# POWER.net
KiCad netlist of a schematic drawn in Altium Designer
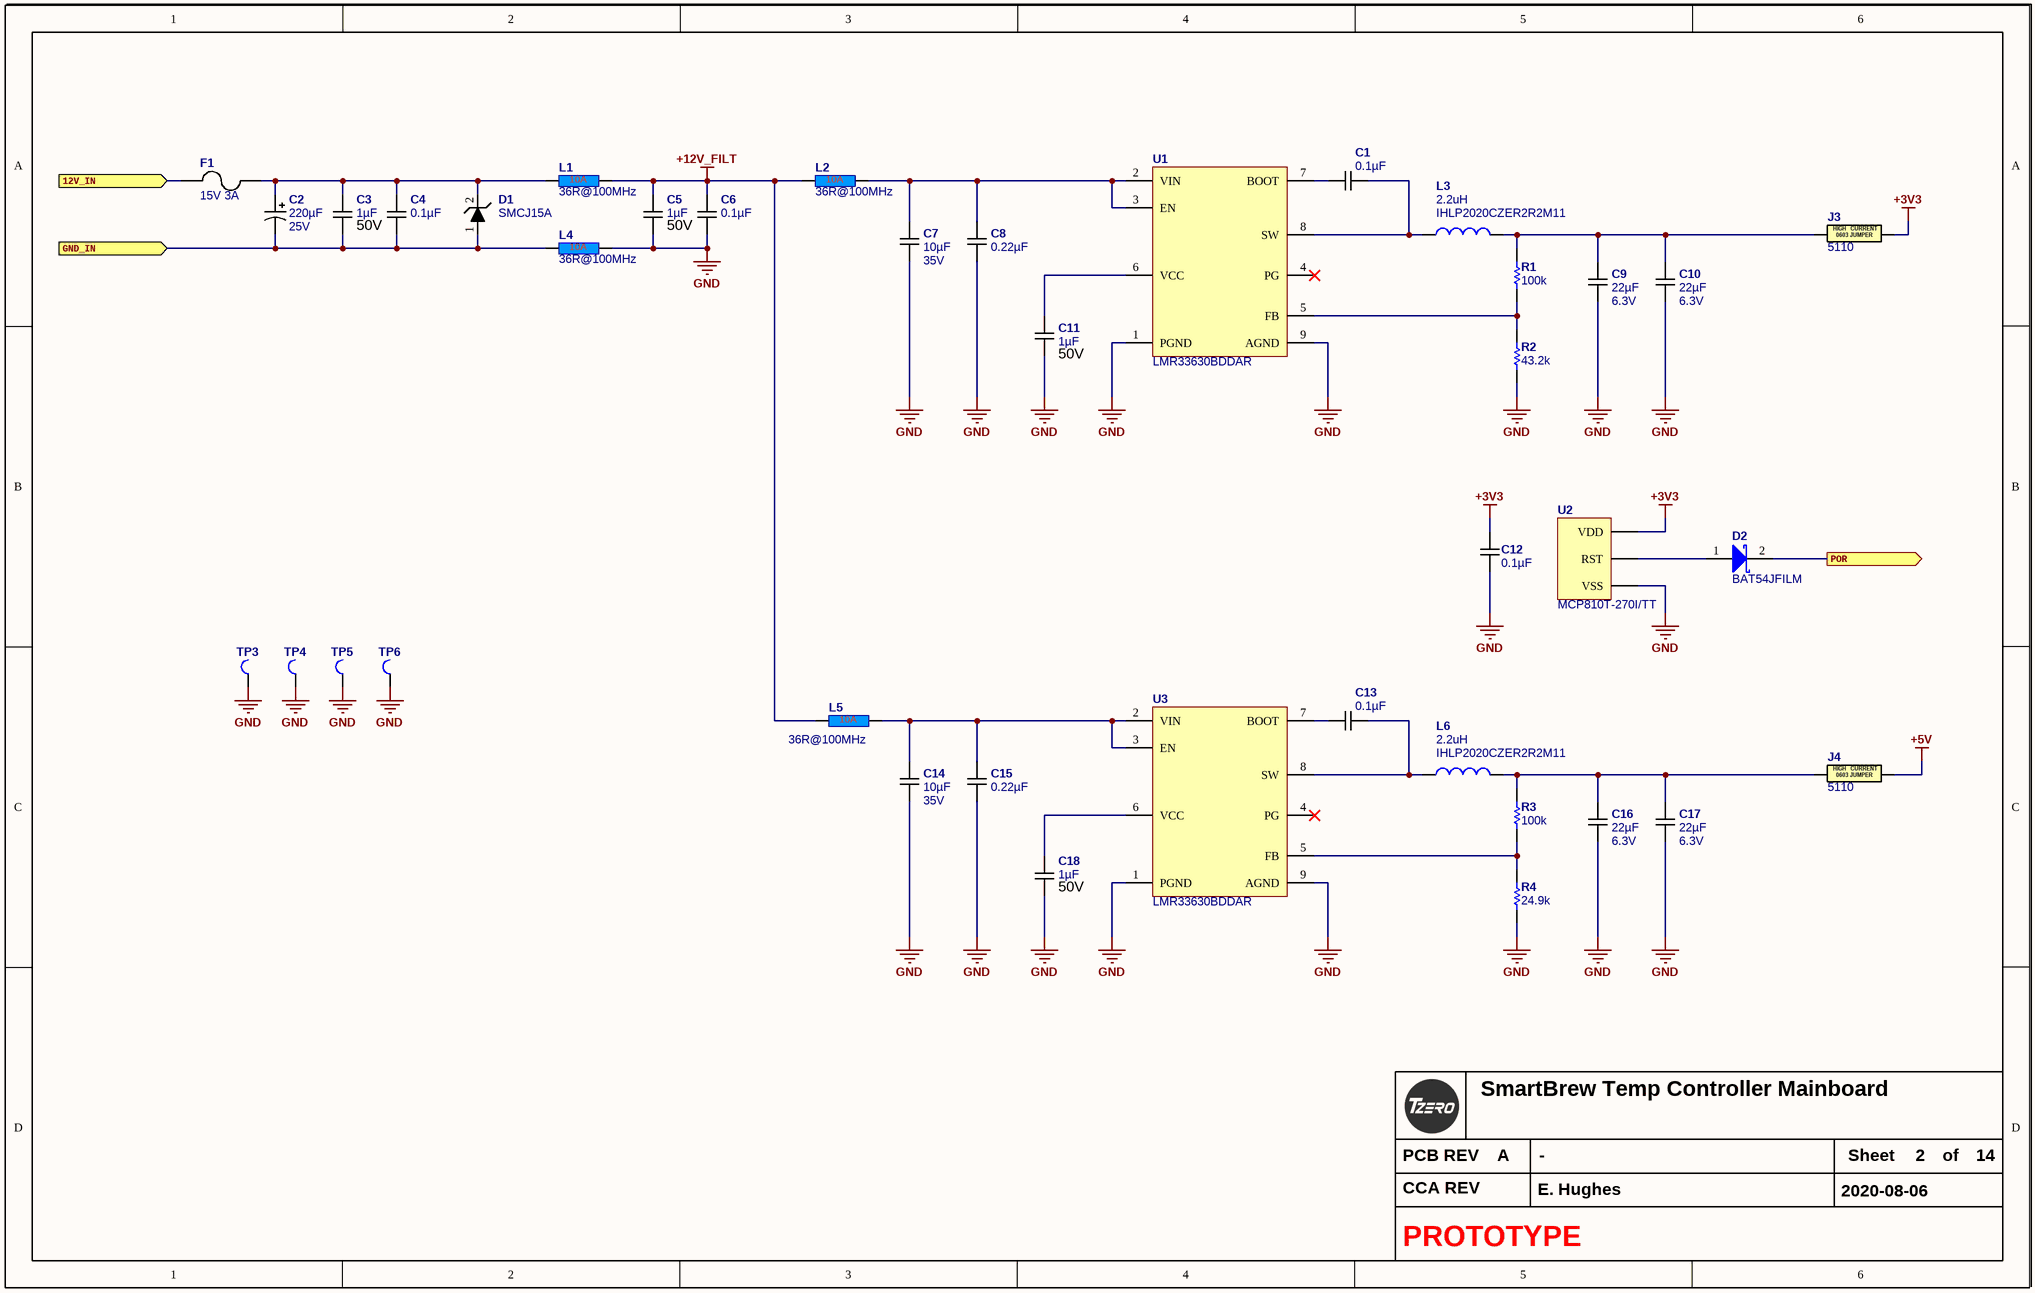
[diagram p0: POWER.SchDoc]

(export (version "E")
  (design (tool "Eeschema 10.0.6"))
  (components
    (comp (ref "C1")
      (value "0.1µF")
      (footprint "C0402_0.55MM_HD")
      (description "CAP CER 0.1UF 25V X7R 0402")
      (fields
        (field (name "MANUFACTURER PART NUMBER") "CGA2B3X7R1E104K050BB")
        (field (name "MANUFACTURER") "TDK Corporation")
      )
      (libsource (lib "Capacitors - TDK- AEC-Q200") (part "C_2P_NP"))
    )
    (comp (ref "C2")
      (value "220µF")
      (footprint "C_ALU_F")
      (description "CAP ALUM 220UF 25V 20% SMD")
      (fields
        (field (name "MANUFACTURER PART NUMBER") "EEE-FK1E221P")
        (field (name "MANUFACTURER") "Panasonic Electronic Components")
        (field (name "VOLTAGE RATING") "25V")
      )
      (libsource (lib "Capacitors - Panasonic - AluminumElectrolytic - AEC-Q200") (part "C_2P_P"))
    )
    (comp (ref "C3")
      (value "1µF")
      (footprint "C0805_1.50MM_MD")
      (description "CAP CER 1UF 50V X7R 0805")
      (fields
        (field (name "MANUFACTURER PART NUMBER") "CGA4J3X7R1H105M125AE")
        (field (name "MANUFACTURER") "TDK Corporation")
        (field (name "VOLTAGE - RATED") "50V")
      )
      (libsource (lib "Capacitors - TDK- AEC-Q200") (part "C_2P_NP"))
    )
    (comp (ref "C4")
      (value "0.1µF")
      (footprint "C0402_0.55MM_HD")
      (description "CAP CER 0.1UF 25V X7R 0402")
      (fields
        (field (name "MANUFACTURER PART NUMBER") "CGA2B3X7R1E104K050BB")
        (field (name "MANUFACTURER") "TDK Corporation")
      )
      (libsource (lib "Capacitors - TDK- AEC-Q200") (part "C_2P_NP"))
    )
    (comp (ref "C5")
      (value "1µF")
      (footprint "C0805_1.50MM_MD")
      (description "CAP CER 1UF 50V X7R 0805")
      (fields
        (field (name "MANUFACTURER PART NUMBER") "CGA4J3X7R1H105M125AE")
        (field (name "MANUFACTURER") "TDK Corporation")
        (field (name "VOLTAGE - RATED") "50V")
      )
      (libsource (lib "Capacitors - TDK- AEC-Q200") (part "C_2P_NP"))
    )
    (comp (ref "C6")
      (value "0.1µF")
      (footprint "C0402_0.55MM_HD")
      (description "CAP CER 0.1UF 25V X7R 0402")
      (fields
        (field (name "MANUFACTURER PART NUMBER") "CGA2B3X7R1E104K050BB")
        (field (name "MANUFACTURER") "TDK Corporation")
      )
      (libsource (lib "Capacitors - TDK- AEC-Q200") (part "C_2P_NP"))
    )
    (comp (ref "C7")
      (value "10µF")
      (footprint "C1206_1.90MM_HD")
      (description "CAP CER 10UF 35V X7R 1206")
      (fields
        (field (name "MANUFACTURER PART NUMBER") "CGA5L1X7R1V106M160AE")
        (field (name "MANUFACTURER") "TDK Corporation")
        (field (name "VOLTAGE - RATED") "35V")
      )
      (libsource (lib "Capacitors - TDK- AEC-Q200") (part "C_2P_NP"))
    )
    (comp (ref "C8")
      (value "0.22µF")
      (footprint "C0603_0.90MM_HD")
      (description "CAP CER 0.22UF 50V X7R 0603")
      (fields
        (field (name "MANUFACTURER PART NUMBER") "CGA3E3X7R1H224K080AB")
        (field (name "MANUFACTURER") "TDK Corporation")
      )
      (libsource (lib "Capacitors - TDK- AEC-Q200") (part "C_2P_NP"))
    )
    (comp (ref "C9")
      (value "22µF")
      (footprint "C1206_1.60MM_HD")
      (description "CAP CER 22UF 6.3V X7R 1206")
      (fields
        (field (name "MANUFACTURER PART NUMBER") "CGA5L1X7R0J226M160AC")
        (field (name "MANUFACTURER") "TDK Corporation")
        (field (name "VOLTAGE - RATED") "6.3V")
      )
      (libsource (lib "Capacitors - TDK- AEC-Q200") (part "C_2P_NP"))
    )
    (comp (ref "C10")
      (value "22µF")
      (footprint "C1206_1.60MM_HD")
      (description "CAP CER 22UF 6.3V X7R 1206")
      (fields
        (field (name "MANUFACTURER PART NUMBER") "CGA5L1X7R0J226M160AC")
        (field (name "MANUFACTURER") "TDK Corporation")
        (field (name "VOLTAGE - RATED") "6.3V")
      )
      (libsource (lib "Capacitors - TDK- AEC-Q200") (part "C_2P_NP"))
    )
    (comp (ref "C11")
      (value "1µF")
      (footprint "C0805_1.50MM_MD")
      (description "CAP CER 1UF 50V X7R 0805")
      (fields
        (field (name "MANUFACTURER PART NUMBER") "CGA4J3X7R1H105M125AE")
        (field (name "MANUFACTURER") "TDK Corporation")
        (field (name "VOLTAGE - RATED") "50V")
      )
      (libsource (lib "Capacitors - TDK- AEC-Q200") (part "C_2P_NP"))
    )
    (comp (ref "C12")
      (value "0.1µF")
      (footprint "C0402_0.55MM_HD")
      (description "CAP CER 0.1UF 25V X7R 0402")
      (fields
        (field (name "MANUFACTURER PART NUMBER") "CGA2B3X7R1E104K050BB")
        (field (name "MANUFACTURER") "TDK Corporation")
      )
      (libsource (lib "Capacitors - TDK- AEC-Q200") (part "C_2P_NP"))
    )
    (comp (ref "C13")
      (value "0.1µF")
      (footprint "C0402_0.55MM_HD")
      (description "CAP CER 0.1UF 25V X7R 0402")
      (fields
        (field (name "MANUFACTURER PART NUMBER") "CGA2B3X7R1E104K050BB")
        (field (name "MANUFACTURER") "TDK Corporation")
      )
      (libsource (lib "Capacitors - TDK- AEC-Q200") (part "C_2P_NP"))
    )
    (comp (ref "C14")
      (value "10µF")
      (footprint "C1206_1.90MM_HD")
      (description "CAP CER 10UF 35V X7R 1206")
      (fields
        (field (name "MANUFACTURER PART NUMBER") "CGA5L1X7R1V106M160AE")
        (field (name "MANUFACTURER") "TDK Corporation")
        (field (name "VOLTAGE - RATED") "35V")
      )
      (libsource (lib "Capacitors - TDK- AEC-Q200") (part "C_2P_NP"))
    )
    (comp (ref "C15")
      (value "0.22µF")
      (footprint "C0603_0.90MM_HD")
      (description "CAP CER 0.22UF 50V X7R 0603")
      (fields
        (field (name "MANUFACTURER PART NUMBER") "CGA3E3X7R1H224K080AB")
        (field (name "MANUFACTURER") "TDK Corporation")
      )
      (libsource (lib "Capacitors - TDK- AEC-Q200") (part "C_2P_NP"))
    )
    (comp (ref "C16")
      (value "22µF")
      (footprint "C1206_1.60MM_HD")
      (description "CAP CER 22UF 6.3V X7R 1206")
      (fields
        (field (name "MANUFACTURER PART NUMBER") "CGA5L1X7R0J226M160AC")
        (field (name "MANUFACTURER") "TDK Corporation")
        (field (name "VOLTAGE - RATED") "6.3V")
      )
      (libsource (lib "Capacitors - TDK- AEC-Q200") (part "C_2P_NP"))
    )
    (comp (ref "C17")
      (value "22µF")
      (footprint "C1206_1.60MM_HD")
      (description "CAP CER 22UF 6.3V X7R 1206")
      (fields
        (field (name "MANUFACTURER PART NUMBER") "CGA5L1X7R0J226M160AC")
        (field (name "MANUFACTURER") "TDK Corporation")
        (field (name "VOLTAGE - RATED") "6.3V")
      )
      (libsource (lib "Capacitors - TDK- AEC-Q200") (part "C_2P_NP"))
    )
    (comp (ref "C18")
      (value "1µF")
      (footprint "C0805_1.50MM_MD")
      (description "CAP CER 1UF 50V X7R 0805")
      (fields
        (field (name "MANUFACTURER PART NUMBER") "CGA4J3X7R1H105M125AE")
        (field (name "MANUFACTURER") "TDK Corporation")
        (field (name "VOLTAGE - RATED") "50V")
      )
      (libsource (lib "Capacitors - TDK- AEC-Q200") (part "C_2P_NP"))
    )
    (comp (ref "D1")
      (value "SMCJ15A")
      (footprint "D_SMC_P")
      (description "DIODE TVS 15V 1500W UNI 5% SMC")
      (fields (field (name "MANUFACTURER") "Littelfuse Inc"))
      (libsource (lib "Diodes") (part "DZ_1A_2C"))
    )
    (comp (ref "D2")
      (value "BAT54JFILM")
      (footprint "Diodes-N:SOD-323")
      (description "DIODE SCHOTTKY 40V 300MA SOD323")
      (fields (field (name "MANUFACTURER") "STMicroelectronics"))
      (libsource (lib "Diodes-N") (part "BAT54JFILM"))
    )
    (comp (ref "F1")
      (value "15V 3A")
      (footprint "F_PTC_2920")
      (description "PTC RESETTABLE 15V 3A SMD 2920")
      (fields
        (field (name "MANUFACTURER PART NUMBER") "2920L300/15DR")
        (field (name "MANUFACTURER") "Littelfuse Inc")
      )
      (libsource (lib "Fuses") (part "F_2P"))
    )
    (comp (ref "J3")
      (value "5110")
      (footprint "C0603_0.9mm")
      (description "0603 Solid High Current Jumper")
      (fields (field (name "MANUFACTURER") "Keystone Electronics") (field (name "TOLERANCE") "Jumper"))
      (libsource (lib "eConnector") (part "5110"))
    )
    (comp (ref "J4")
      (value "5110")
      (footprint "C0603_0.9mm")
      (description "0603 Solid High Current Jumper")
      (fields (field (name "MANUFACTURER") "Keystone Electronics") (field (name "TOLERANCE") "Jumper"))
      (libsource (lib "eConnector") (part "5110"))
    )
    (comp (ref "L1")
      (value "36R@100MHz")
      (footprint "T_Laird_35F0121-0SR-10")
      (description "Power Supply FB 10A")
      (fields (field (name "TOLERANCE") "25%") (field (name "MANUFACTURER PART NO.") "35F0121-0SR-10"))
      (libsource (lib "eInductor") (part "35F0121-0SR-10"))
    )
    (comp (ref "L2")
      (value "36R@100MHz")
      (footprint "T_Laird_35F0121-0SR-10")
      (description "Power Supply FB 10A")
      (fields (field (name "TOLERANCE") "25%") (field (name "MANUFACTURER PART NO.") "35F0121-0SR-10"))
      (libsource (lib "eInductor") (part "35F0121-0SR-10"))
    )
    (comp (ref "L3")
      (value "2.2uH")
      (footprint "Inductors - N:IHLP-2020CZ")
      (description "FIXED IND 2.2UH 6.75A 25 MOHM")
      (fields
        (field (name "MANUFACTURER") "Vishay Dale")
        (field (name "MANUFACTURER PART NUMBER") "IHLP2020CZER2R2M11")
        (field (name "TOLERANCE") "20%")
      )
      (libsource (lib "Inductors-N") (part "IHLP2020CZER2R2M11"))
    )
    (comp (ref "L4")
      (value "36R@100MHz")
      (footprint "T_Laird_35F0121-0SR-10")
      (description "Power Supply FB 10A")
      (fields (field (name "TOLERANCE") "25%") (field (name "MANUFACTURER PART NO.") "35F0121-0SR-10"))
      (libsource (lib "eInductor") (part "35F0121-0SR-10"))
    )
    (comp (ref "L5")
      (value "36R@100MHz")
      (footprint "T_Laird_35F0121-0SR-10")
      (description "Power Supply FB 10A")
      (fields (field (name "TOLERANCE") "25%") (field (name "MANUFACTURER PART NO.") "35F0121-0SR-10"))
      (libsource (lib "eInductor") (part "35F0121-0SR-10"))
    )
    (comp (ref "L6")
      (value "2.2uH")
      (footprint "Inductors - N:IHLP-2020CZ")
      (description "FIXED IND 2.2UH 6.75A 25 MOHM")
      (fields
        (field (name "MANUFACTURER") "Vishay Dale")
        (field (name "MANUFACTURER PART NUMBER") "IHLP2020CZER2R2M11")
        (field (name "TOLERANCE") "20%")
      )
      (libsource (lib "Inductors-N") (part "IHLP2020CZER2R2M11"))
    )
    (comp (ref "R1")
      (value "100k")
      (footprint "R0603_0.55MM_MD")
      (description "RES 100K OHM 1/10W 1% 0603 SMD")
      (fields
        (field (name "MANUFACTURER PART NUMBER") "ERJ-3EKF1003V")
        (field (name "MANUFACTURER") "Panasonic Electronic Components")
      )
      (libsource (lib "Resistors - Panasonic - AEC-Q200") (part "R_2P"))
    )
    (comp (ref "R2")
      (value "43.2k")
      (footprint "R0603_0.55MM_MD")
      (description "RES 43.2K OHM 1/10W 1% 0603 SMD")
      (fields
        (field (name "MANUFACTURER PART NUMBER") "ERJ-3EKF4322V")
        (field (name "MANUFACTURER") "Panasonic Electronic Components")
      )
      (libsource (lib "Resistors - Panasonic - AEC-Q200") (part "R_2P"))
    )
    (comp (ref "R3")
      (value "100k")
      (footprint "R0603_0.55MM_MD")
      (description "RES 100K OHM 1/10W 1% 0603 SMD")
      (fields
        (field (name "MANUFACTURER PART NUMBER") "ERJ-3EKF1003V")
        (field (name "MANUFACTURER") "Panasonic Electronic Components")
      )
      (libsource (lib "Resistors - Panasonic - AEC-Q200") (part "R_2P"))
    )
    (comp (ref "R4")
      (value "24.9k")
      (footprint "R0603_0.55MM_MD")
      (description "RES 24.9K OHM 1/10W 1% 0603 SMD")
      (fields
        (field (name "MANUFACTURER PART NUMBER") "ERJ-3EKF2492V")
        (field (name "MANUFACTURER") "Panasonic Electronic Components")
      )
      (libsource (lib "Resistors - Panasonic - AEC-Q200") (part "R_2P"))
    )
    (comp (ref "TP3")
      (value "PC TEST POINT MINIATURE SMT")
      (footprint "SMT_TEST_5015")
      (fields
        (field (name "MANUFACTURER") "Keystone Electronics")
        (field (name "MANUFACTURER PART NUMBER") "5015")
      )
      (libsource (lib "eConnector") (part "5015"))
    )
    (comp (ref "TP4")
      (value "PC TEST POINT MINIATURE SMT")
      (footprint "SMT_TEST_5015")
      (fields
        (field (name "MANUFACTURER") "Keystone Electronics")
        (field (name "MANUFACTURER PART NUMBER") "5015")
      )
      (libsource (lib "eConnector") (part "5015"))
    )
    (comp (ref "TP5")
      (value "PC TEST POINT MINIATURE SMT")
      (footprint "SMT_TEST_5015")
      (fields
        (field (name "MANUFACTURER") "Keystone Electronics")
        (field (name "MANUFACTURER PART NUMBER") "5015")
      )
      (libsource (lib "eConnector") (part "5015"))
    )
    (comp (ref "TP6")
      (value "PC TEST POINT MINIATURE SMT")
      (footprint "SMT_TEST_5015")
      (fields
        (field (name "MANUFACTURER") "Keystone Electronics")
        (field (name "MANUFACTURER PART NUMBER") "5015")
      )
      (libsource (lib "eConnector") (part "5015"))
    )
    (comp (ref "U1")
      (value "LMR33630BDDAR")
      (footprint "Integrated Circuits SMT-N:HSOIC-8")
      (fields (field (name "MANUFACTURER") "Texas Instruments"))
      (libsource (lib "Texas Instruments-N") (part "LMR33630BDDAR"))
    )
    (comp (ref "U2")
      (value "MCP810T-270I/TT")
      (footprint "Integrated Circuits SMT-N:SOT23_Medium")
      (description "IC SUPERVISOR 2.70V HIGH SOT23")
      (fields (field (name "MANUFACTURER") "Microchip Technology"))
      (libsource (lib "Microchip-N") (part "MCP810T-270I/TT"))
    )
    (comp (ref "U3")
      (value "LMR33630BDDAR")
      (footprint "Integrated Circuits SMT-N:HSOIC-8")
      (fields (field (name "MANUFACTURER") "Texas Instruments"))
      (libsource (lib "Texas Instruments-N") (part "LMR33630BDDAR"))
    )
  )
  (nets
    (net (code "1") (name "+3V3") (class "Default")
      (node (ref "C12") (pin "1") (pinfunction "1_1") (pintype "passive"))
      (node (ref "J3") (pin "2") (pinfunction "2_2") (pintype "passive"))
      (node (ref "U2") (pin "3") (pinfunction "VDD_3") (pintype "passive"))
    )
    (net (code "2") (name "+5V") (class "Default")
      (node (ref "J4") (pin "2") (pinfunction "2_2") (pintype "passive"))
    )
    (net (code "3") (name "+12V_FILT") (class "Default")
      (node (ref "C5") (pin "2") (pinfunction "1_2") (pintype "passive"))
      (node (ref "C6") (pin "2") (pinfunction "1_2") (pintype "passive"))
      (node (ref "L1") (pin "2") (pinfunction "2_2") (pintype "passive"))
      (node (ref "L2") (pin "1") (pinfunction "1_1") (pintype "passive"))
      (node (ref "L5") (pin "1") (pinfunction "1_1") (pintype "passive"))
    )
    (net (code "4") (name "/12V_IN") (class "Default")
      (node (ref "F1") (pin "1") (pinfunction "1_1") (pintype "passive"))
    )
    (net (code "5") (name "/GND_IN") (class "Default")
      (node (ref "C2") (pin "2") (pinfunction "1_2") (pintype "passive"))
      (node (ref "C3") (pin "1") (pinfunction "1_1") (pintype "passive"))
      (node (ref "C4") (pin "1") (pinfunction "1_1") (pintype "passive"))
      (node (ref "D1") (pin "1") (pinfunction "A_1") (pintype "passive"))
      (node (ref "L4") (pin "1") (pinfunction "1_1") (pintype "passive"))
    )
    (net (code "6") (name "/POR") (class "Default")
      (node (ref "D2") (pin "2") (pinfunction "K_2") (pintype "passive"))
    )
    (net (code "7") (name "GND") (class "Default")
      (node (ref "C10") (pin "1") (pinfunction "1_1") (pintype "passive"))
      (node (ref "C11") (pin "1") (pinfunction "1_1") (pintype "passive"))
      (node (ref "C12") (pin "2") (pinfunction "1_2") (pintype "passive"))
      (node (ref "C14") (pin "1") (pinfunction "1_1") (pintype "passive"))
      (node (ref "C15") (pin "1") (pinfunction "1_1") (pintype "passive"))
      (node (ref "C16") (pin "1") (pinfunction "1_1") (pintype "passive"))
      (node (ref "C17") (pin "1") (pinfunction "1_1") (pintype "passive"))
      (node (ref "C18") (pin "1") (pinfunction "1_1") (pintype "passive"))
      (node (ref "C5") (pin "1") (pinfunction "1_1") (pintype "passive"))
      (node (ref "C6") (pin "1") (pinfunction "1_1") (pintype "passive"))
      (node (ref "C7") (pin "1") (pinfunction "1_1") (pintype "passive"))
      (node (ref "C8") (pin "1") (pinfunction "1_1") (pintype "passive"))
      (node (ref "C9") (pin "1") (pinfunction "1_1") (pintype "passive"))
      (node (ref "L4") (pin "2") (pinfunction "2_2") (pintype "passive"))
      (node (ref "R2") (pin "1") (pinfunction "1_1") (pintype "passive"))
      (node (ref "R4") (pin "1") (pinfunction "1_1") (pintype "passive"))
      (node (ref "TP3") (pin "1") (pinfunction "1_1") (pintype "passive"))
      (node (ref "TP4") (pin "1") (pinfunction "1_1") (pintype "passive"))
      (node (ref "TP5") (pin "1") (pinfunction "1_1") (pintype "passive"))
      (node (ref "TP6") (pin "1") (pinfunction "1_1") (pintype "passive"))
      (node (ref "U1") (pin "1") (pinfunction "PGND_1") (pintype "passive"))
      (node (ref "U1") (pin "9") (pinfunction "AGND_9") (pintype "passive"))
      (node (ref "U2") (pin "1") (pinfunction "VSS_1") (pintype "passive"))
      (node (ref "U3") (pin "1") (pinfunction "PGND_1") (pintype "passive"))
      (node (ref "U3") (pin "9") (pinfunction "AGND_9") (pintype "passive"))
    )
    (net (code "8") (name "Net-(C10-1-Pad2)") (class "Default")
      (node (ref "C10") (pin "2") (pinfunction "1_2") (pintype "passive"))
      (node (ref "C9") (pin "2") (pinfunction "1_2") (pintype "passive"))
      (node (ref "J3") (pin "1") (pinfunction "1_1") (pintype "passive"))
      (node (ref "L3") (pin "2") (pinfunction "2_2") (pintype "passive"))
      (node (ref "R1") (pin "2") (pinfunction "2_2") (pintype "passive"))
    )
    (net (code "9") (name "Net-(C16-1-Pad2)") (class "Default")
      (node (ref "C16") (pin "2") (pinfunction "1_2") (pintype "passive"))
      (node (ref "C17") (pin "2") (pinfunction "1_2") (pintype "passive"))
      (node (ref "J4") (pin "1") (pinfunction "1_1") (pintype "passive"))
      (node (ref "L6") (pin "2") (pinfunction "2_2") (pintype "passive"))
      (node (ref "R3") (pin "2") (pinfunction "2_2") (pintype "passive"))
    )
    (net (code "10") (name "Net-(D1-K)") (class "Default")
      (node (ref "C2") (pin "1") (pinfunction "1_1") (pintype "passive"))
      (node (ref "C3") (pin "2") (pinfunction "1_2") (pintype "passive"))
      (node (ref "C4") (pin "2") (pinfunction "1_2") (pintype "passive"))
      (node (ref "D1") (pin "2") (pinfunction "K_2") (pintype "passive"))
      (node (ref "F1") (pin "2") (pinfunction "2_2") (pintype "passive"))
      (node (ref "L1") (pin "1") (pinfunction "1_1") (pintype "passive"))
    )
    (net (code "11") (name "Net-(D2-A)") (class "Default")
      (node (ref "D2") (pin "1") (pinfunction "A_1") (pintype "passive"))
      (node (ref "U2") (pin "2") (pinfunction "RST_2") (pintype "passive"))
    )
    (net (code "12") (name "Net-(U1-BOOT)") (class "Default")
      (node (ref "C1") (pin "2") (pinfunction "1_2") (pintype "passive"))
      (node (ref "U1") (pin "7") (pinfunction "BOOT_7") (pintype "passive"))
    )
    (net (code "13") (name "Net-(U1-EN)") (class "Default")
      (node (ref "C7") (pin "2") (pinfunction "1_2") (pintype "passive"))
      (node (ref "C8") (pin "2") (pinfunction "1_2") (pintype "passive"))
      (node (ref "L2") (pin "2") (pinfunction "2_2") (pintype "passive"))
      (node (ref "U1") (pin "2") (pinfunction "VIN_2") (pintype "passive"))
      (node (ref "U1") (pin "3") (pinfunction "EN_3") (pintype "passive"))
    )
    (net (code "14") (name "Net-(U1-FB)") (class "Default")
      (node (ref "R1") (pin "1") (pinfunction "1_1") (pintype "passive"))
      (node (ref "R2") (pin "2") (pinfunction "2_2") (pintype "passive"))
      (node (ref "U1") (pin "5") (pinfunction "FB_5") (pintype "passive"))
    )
    (net (code "15") (name "Net-(U1-SW)") (class "Default")
      (node (ref "C1") (pin "1") (pinfunction "1_1") (pintype "passive"))
      (node (ref "L3") (pin "1") (pinfunction "1_1") (pintype "passive"))
      (node (ref "U1") (pin "8") (pinfunction "SW_8") (pintype "passive"))
    )
    (net (code "16") (name "Net-(U1-VCC)") (class "Default")
      (node (ref "C11") (pin "2") (pinfunction "1_2") (pintype "passive"))
      (node (ref "U1") (pin "6") (pinfunction "VCC_6") (pintype "passive"))
    )
    (net (code "17") (name "Net-(U3-BOOT)") (class "Default")
      (node (ref "C13") (pin "2") (pinfunction "1_2") (pintype "passive"))
      (node (ref "U3") (pin "7") (pinfunction "BOOT_7") (pintype "passive"))
    )
    (net (code "18") (name "Net-(U3-EN)") (class "Default")
      (node (ref "C14") (pin "2") (pinfunction "1_2") (pintype "passive"))
      (node (ref "C15") (pin "2") (pinfunction "1_2") (pintype "passive"))
      (node (ref "L5") (pin "2") (pinfunction "2_2") (pintype "passive"))
      (node (ref "U3") (pin "2") (pinfunction "VIN_2") (pintype "passive"))
      (node (ref "U3") (pin "3") (pinfunction "EN_3") (pintype "passive"))
    )
    (net (code "19") (name "Net-(U3-FB)") (class "Default")
      (node (ref "R3") (pin "1") (pinfunction "1_1") (pintype "passive"))
      (node (ref "R4") (pin "2") (pinfunction "2_2") (pintype "passive"))
      (node (ref "U3") (pin "5") (pinfunction "FB_5") (pintype "passive"))
    )
    (net (code "20") (name "Net-(U3-SW)") (class "Default")
      (node (ref "C13") (pin "1") (pinfunction "1_1") (pintype "passive"))
      (node (ref "L6") (pin "1") (pinfunction "1_1") (pintype "passive"))
      (node (ref "U3") (pin "8") (pinfunction "SW_8") (pintype "passive"))
    )
    (net (code "21") (name "Net-(U3-VCC)") (class "Default")
      (node (ref "C18") (pin "2") (pinfunction "1_2") (pintype "passive"))
      (node (ref "U3") (pin "6") (pinfunction "VCC_6") (pintype "passive"))
    )
    (net (code "22") (name "unconnected-(U1-PG-Pad4)") (class "Default")
      (node (ref "U1") (pin "4") (pinfunction "PG_4") (pintype "passive+no_connect"))
    )
    (net (code "23") (name "unconnected-(U3-PG-Pad4)") (class "Default")
      (node (ref "U3") (pin "4") (pinfunction "PG_4") (pintype "passive+no_connect"))
    )
  )
)
